# MEM.net
KiCad netlist of a schematic drawn in Altium Designer
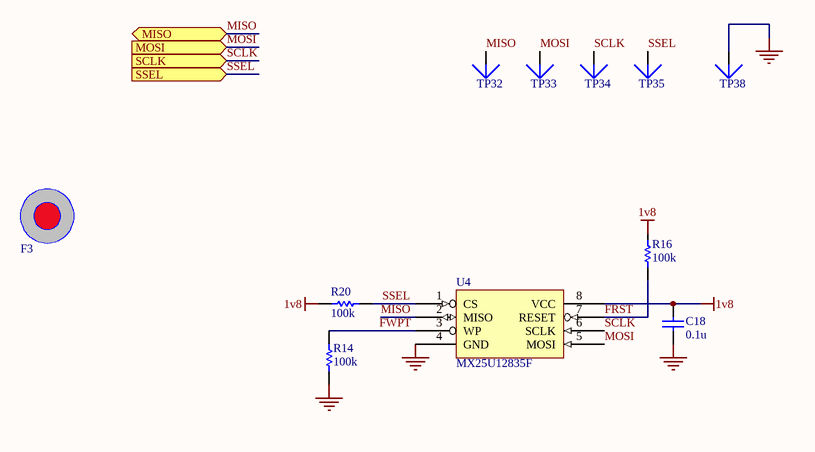
[diagram p0: MEM.SchDoc]

(export (version "E")
  (design (tool "Eeschema 10.0.6"))
  (components
    (comp (ref "C18")
      (value "0.1u")
      (footprint "CAP0201")
      (description "Chip capacitor")
      (fields (field (name "TOLERANCE") "10%") (field (name "VOLTAGE") "6.3"))
      (libsource (lib "Hello") (part "C_0.1u_10_6.3_X5R_0201"))
    )
    (comp (ref "F3")
      (value "Fiducial")
      (footprint "Fiducial-0.5")
      (description "Fiducial with 0.5mm radius and 0.5mm paste expansion")
      (libsource (lib "Hello") (part "Fiducial-0.5"))
    )
    (comp (ref "R14")
      (value "100k")
      (footprint "RES0201")
      (description "Chip Resistor")
      (fields (field (name "TOLERANCE") "5 %") (field (name "POWER") "0.05 W"))
      (libsource (lib "Hello") (part "R_100k_5_0.05_0201"))
    )
    (comp (ref "R16")
      (value "100k")
      (footprint "RES0201")
      (description "Chip Resistor")
      (fields (field (name "TOLERANCE") "5 %") (field (name "POWER") "0.05 W"))
      (libsource (lib "Hello") (part "R_100k_5_0.05_0201"))
    )
    (comp (ref "R20")
      (value "100k")
      (footprint "RES0201")
      (description "Chip Resistor")
      (fields (field (name "TOLERANCE") "5 %") (field (name "POWER") "0.05 W"))
      (libsource (lib "Hello") (part "R_100k_5_0.05_0201"))
    )
    (comp (ref "TP32")
      (value "TestPoint")
      (footprint "TP-0.3")
      (description "Generic Test Point")
      (libsource (lib "Hello") (part "TestPoint"))
    )
    (comp (ref "TP33")
      (value "TestPoint")
      (footprint "TP-0.3")
      (description "Generic Test Point")
      (libsource (lib "Hello") (part "TestPoint"))
    )
    (comp (ref "TP34")
      (value "TestPoint")
      (footprint "TP-0.3")
      (description "Generic Test Point")
      (libsource (lib "Hello") (part "TestPoint"))
    )
    (comp (ref "TP35")
      (value "TestPoint")
      (footprint "TP-0.3")
      (description "Generic Test Point")
      (libsource (lib "Hello") (part "TestPoint"))
    )
    (comp (ref "TP38")
      (value "TestPoint")
      (footprint "TP-0.3")
      (description "Generic Test Point")
      (libsource (lib "Hello") (part "TestPoint"))
    )
    (comp (ref "U4")
      (value "MX25U12835F")
      (footprint "WSON 8L")
      (description "Macronix MX25U12835F SPI NOR Flash")
      (libsource (lib "Hello") (part "MX25U12835F"))
    )
  )
  (nets
    (net (code "1") (name "/FRST") (class "Default")
      (node (ref "R16") (pin "1") (pinfunction "1_1") (pintype "passive"))
      (node (ref "U4") (pin "7") (pinfunction "RESET_7") (pintype "input"))
    )
    (net (code "2") (name "/FWPT") (class "Default")
      (node (ref "R14") (pin "2") (pinfunction "2_2") (pintype "passive"))
      (node (ref "U4") (pin "3") (pinfunction "WP_3") (pintype "passive"))
    )
    (net (code "3") (name "/MISO") (class "Default")
      (node (ref "TP32") (pin "1") (pinfunction "1_1") (pintype "passive"))
      (node (ref "U4") (pin "2") (pinfunction "MISO_2") (pintype "bidirectional"))
    )
    (net (code "4") (name "/MOSI") (class "Default")
      (node (ref "TP33") (pin "1") (pinfunction "1_1") (pintype "passive"))
      (node (ref "U4") (pin "5") (pinfunction "MOSI_5") (pintype "input"))
    )
    (net (code "5") (name "/SCLK") (class "Default")
      (node (ref "TP34") (pin "1") (pinfunction "1_1") (pintype "passive"))
      (node (ref "U4") (pin "6") (pinfunction "SCLK_6") (pintype "input"))
    )
    (net (code "6") (name "/SSEL") (class "Default")
      (node (ref "R20") (pin "2") (pinfunction "2_2") (pintype "passive"))
      (node (ref "TP35") (pin "1") (pinfunction "1_1") (pintype "passive"))
      (node (ref "U4") (pin "1") (pinfunction "CS_1") (pintype "input"))
    )
    (net (code "7") (name "1v8") (class "Default")
      (node (ref "C18") (pin "2") (pinfunction "2_2") (pintype "passive"))
      (node (ref "R20") (pin "1") (pinfunction "1_1") (pintype "passive"))
      (node (ref "U4") (pin "8") (pinfunction "VCC_8") (pintype "power_in"))
    )
    (net (code "8") (name "GND") (class "Default")
      (node (ref "C18") (pin "1") (pinfunction "1_1") (pintype "passive"))
      (node (ref "R14") (pin "1") (pinfunction "1_1") (pintype "passive"))
      (node (ref "TP38") (pin "1") (pinfunction "1_1") (pintype "passive"))
      (node (ref "U4") (pin "4") (pinfunction "GND_4") (pintype "power_in"))
    )
    (net (code "9") (name "unconnected-(R16-Pad2)") (class "Default")
      (node (ref "R16") (pin "2") (pinfunction "2_2") (pintype "passive"))
    )
  )
)
